# PT08Mpld.net
KiCad netlist of a schematic drawn in EAGLE
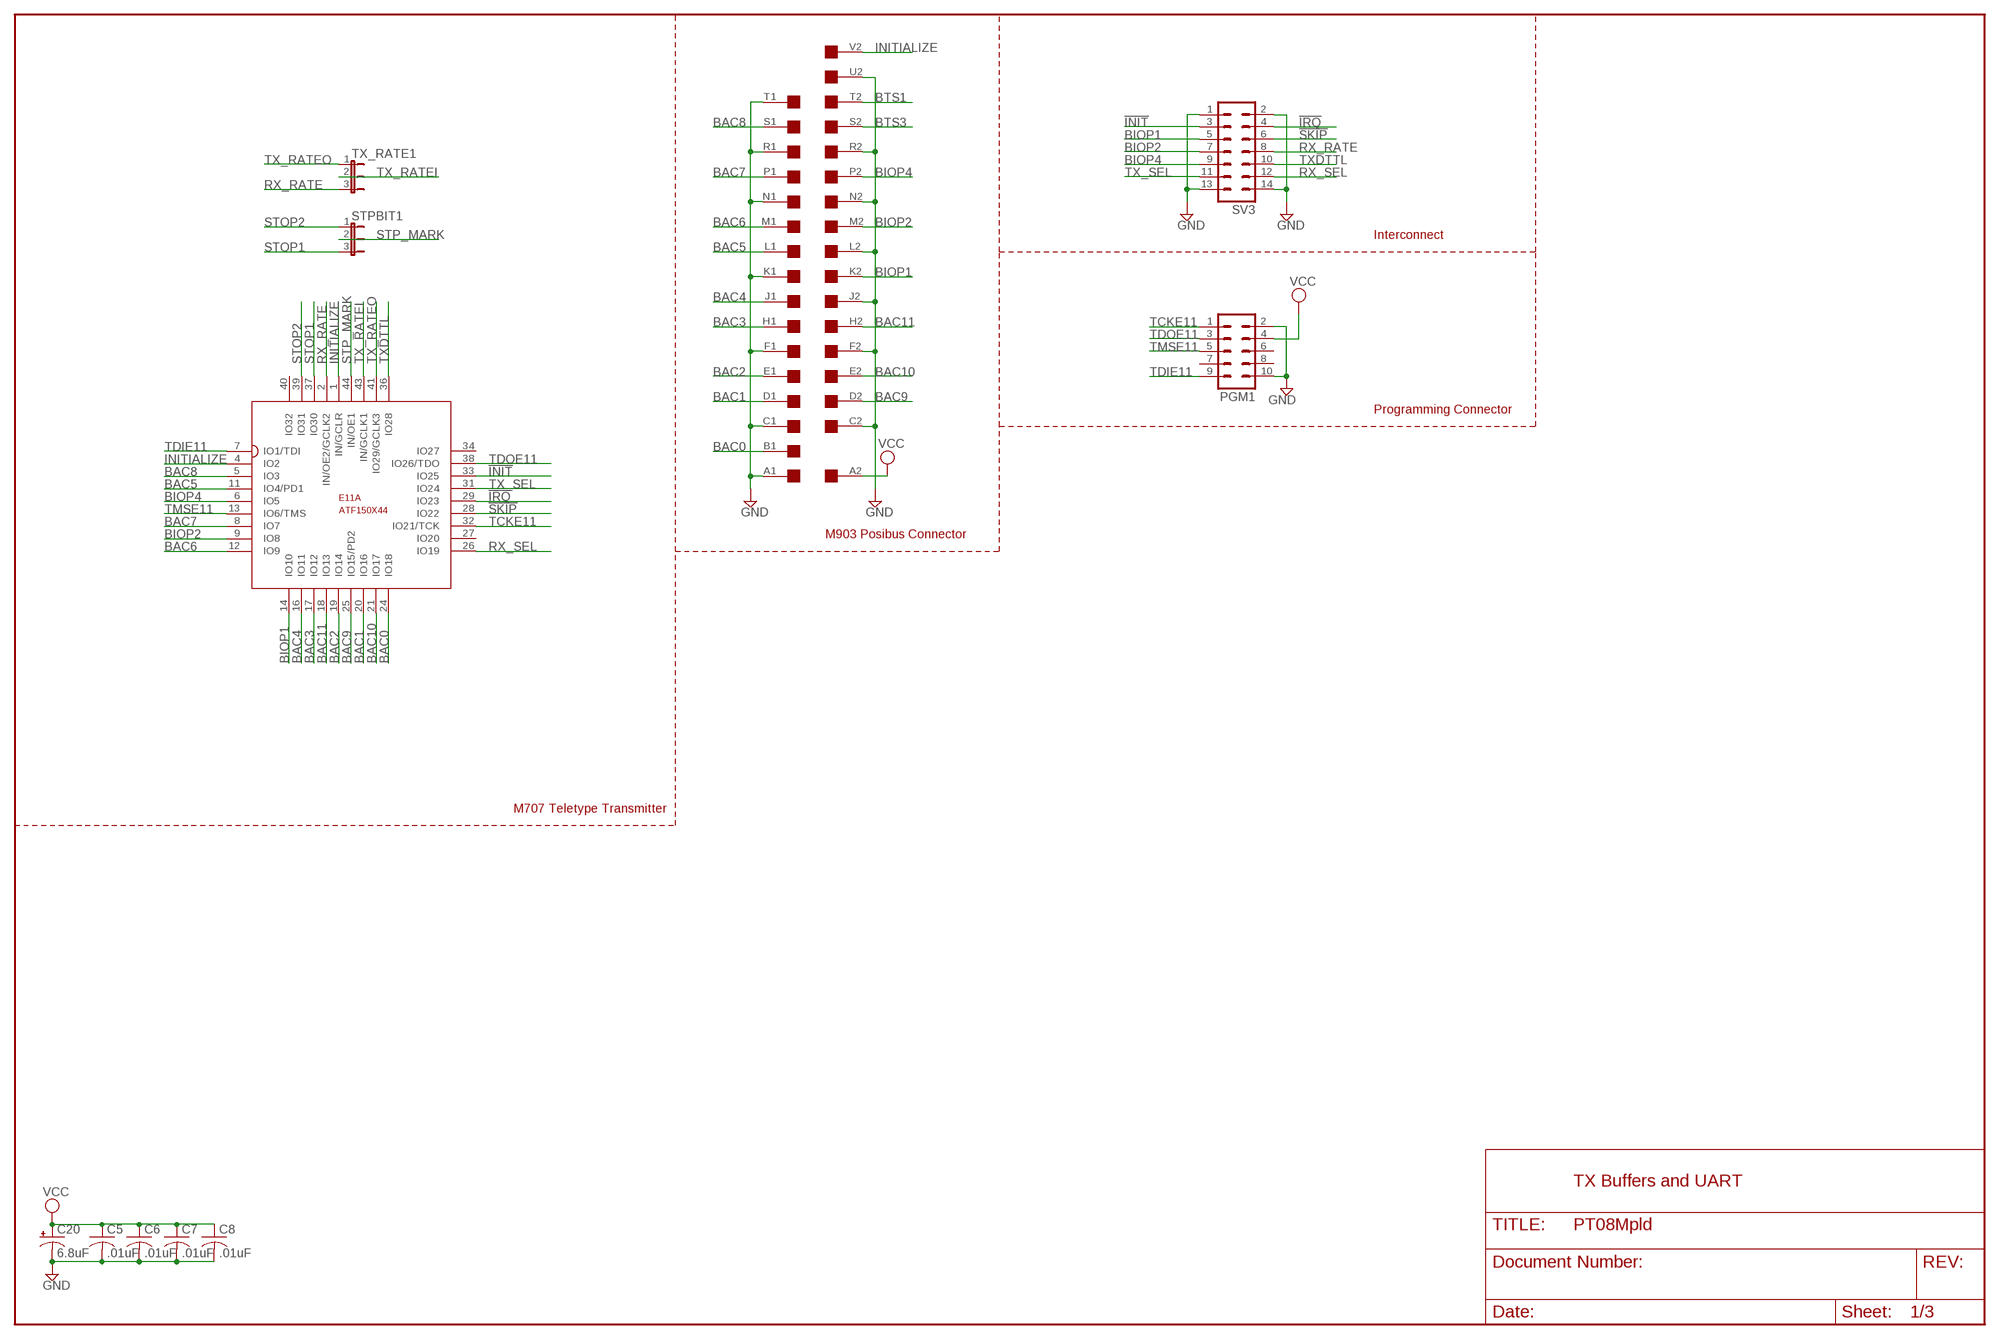
[diagram p0: schematic, sheet 1]
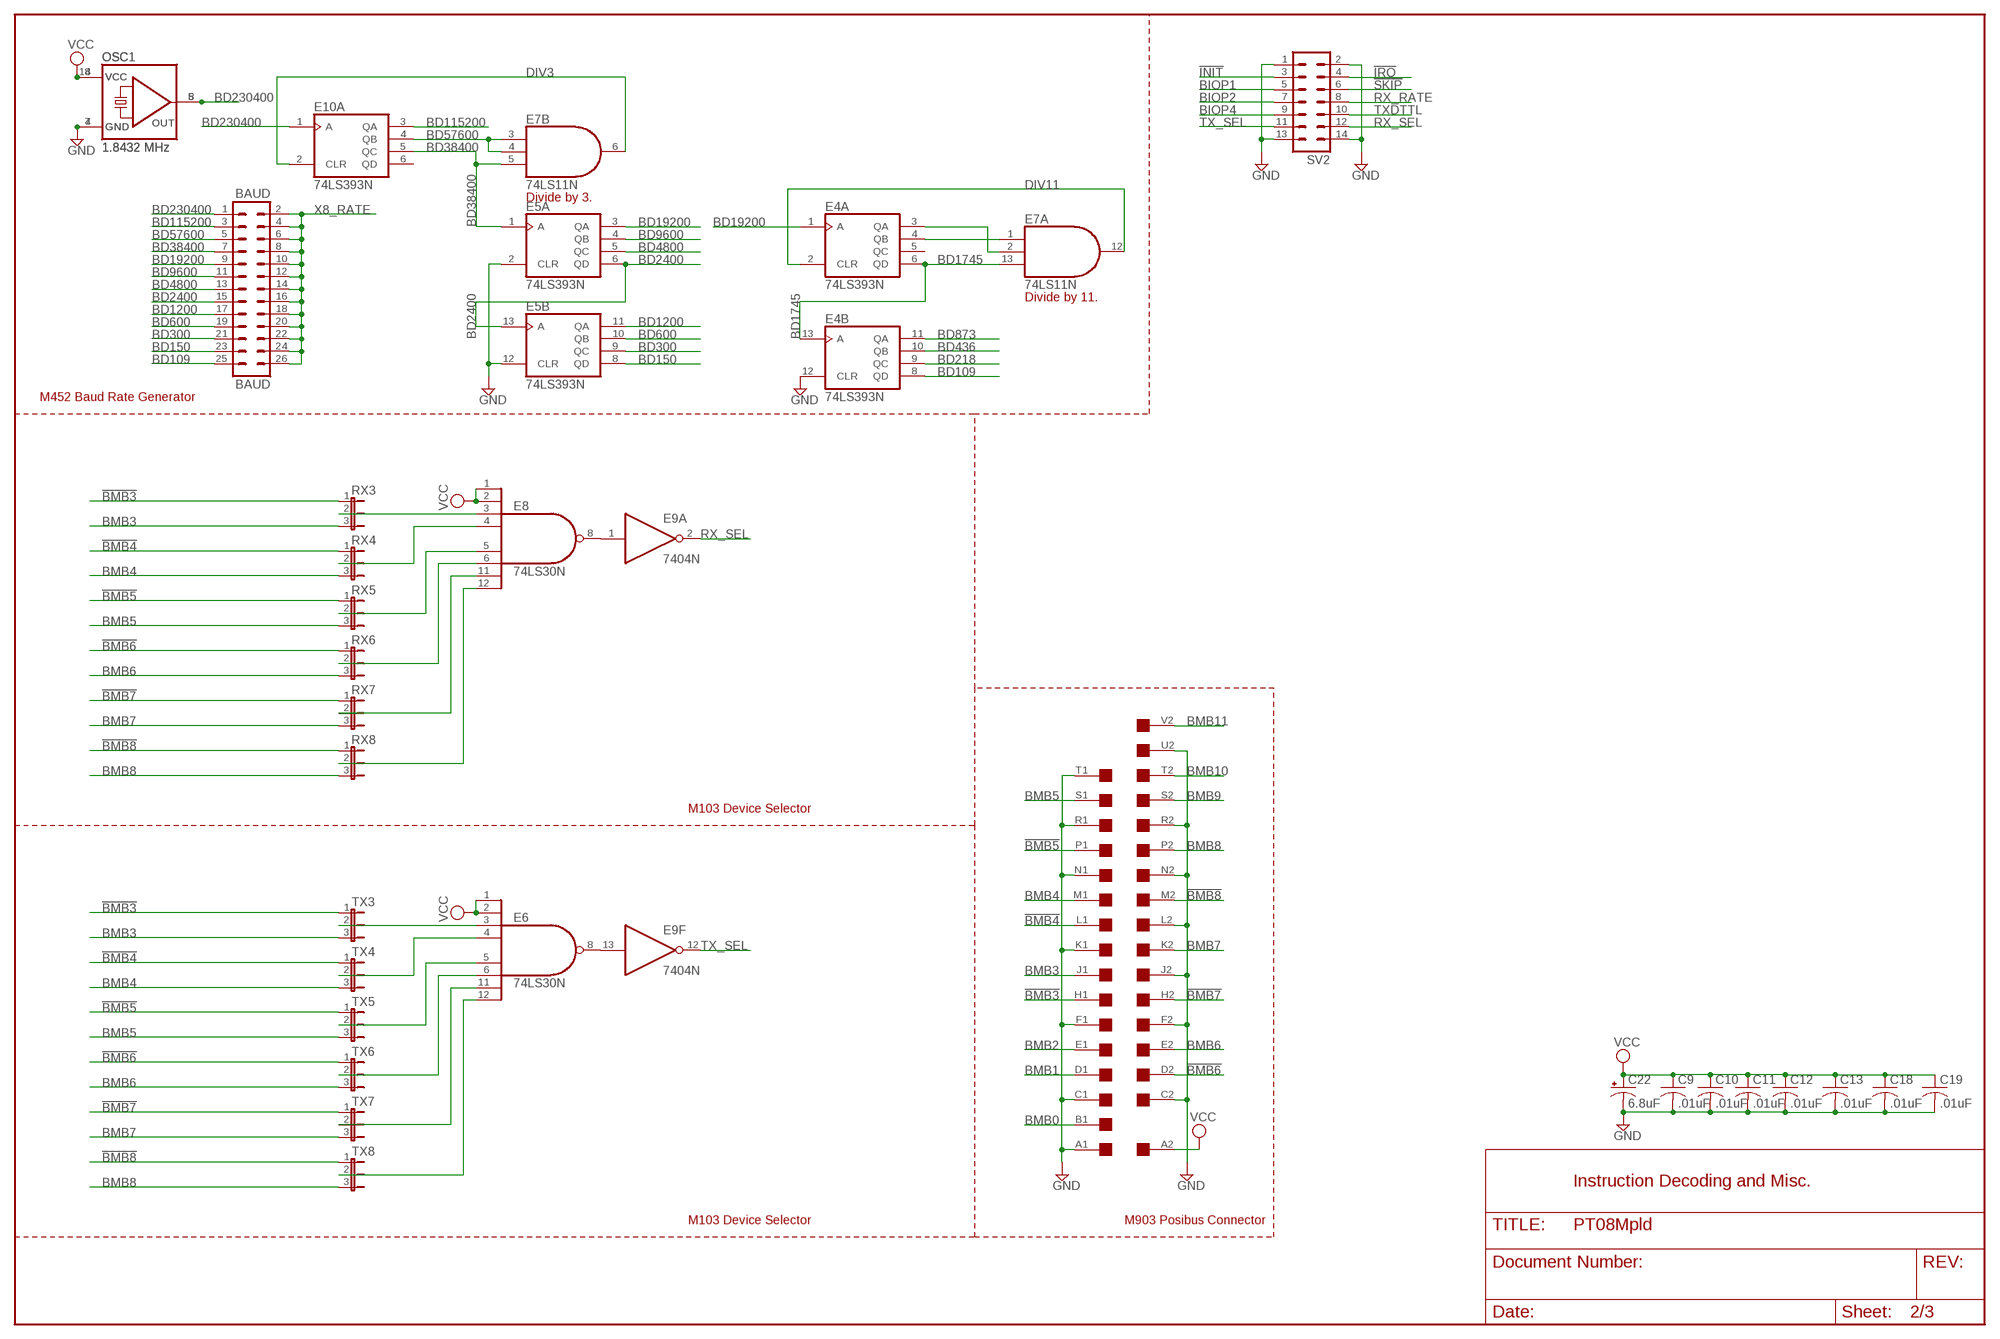
[diagram p1: schematic, sheet 2]
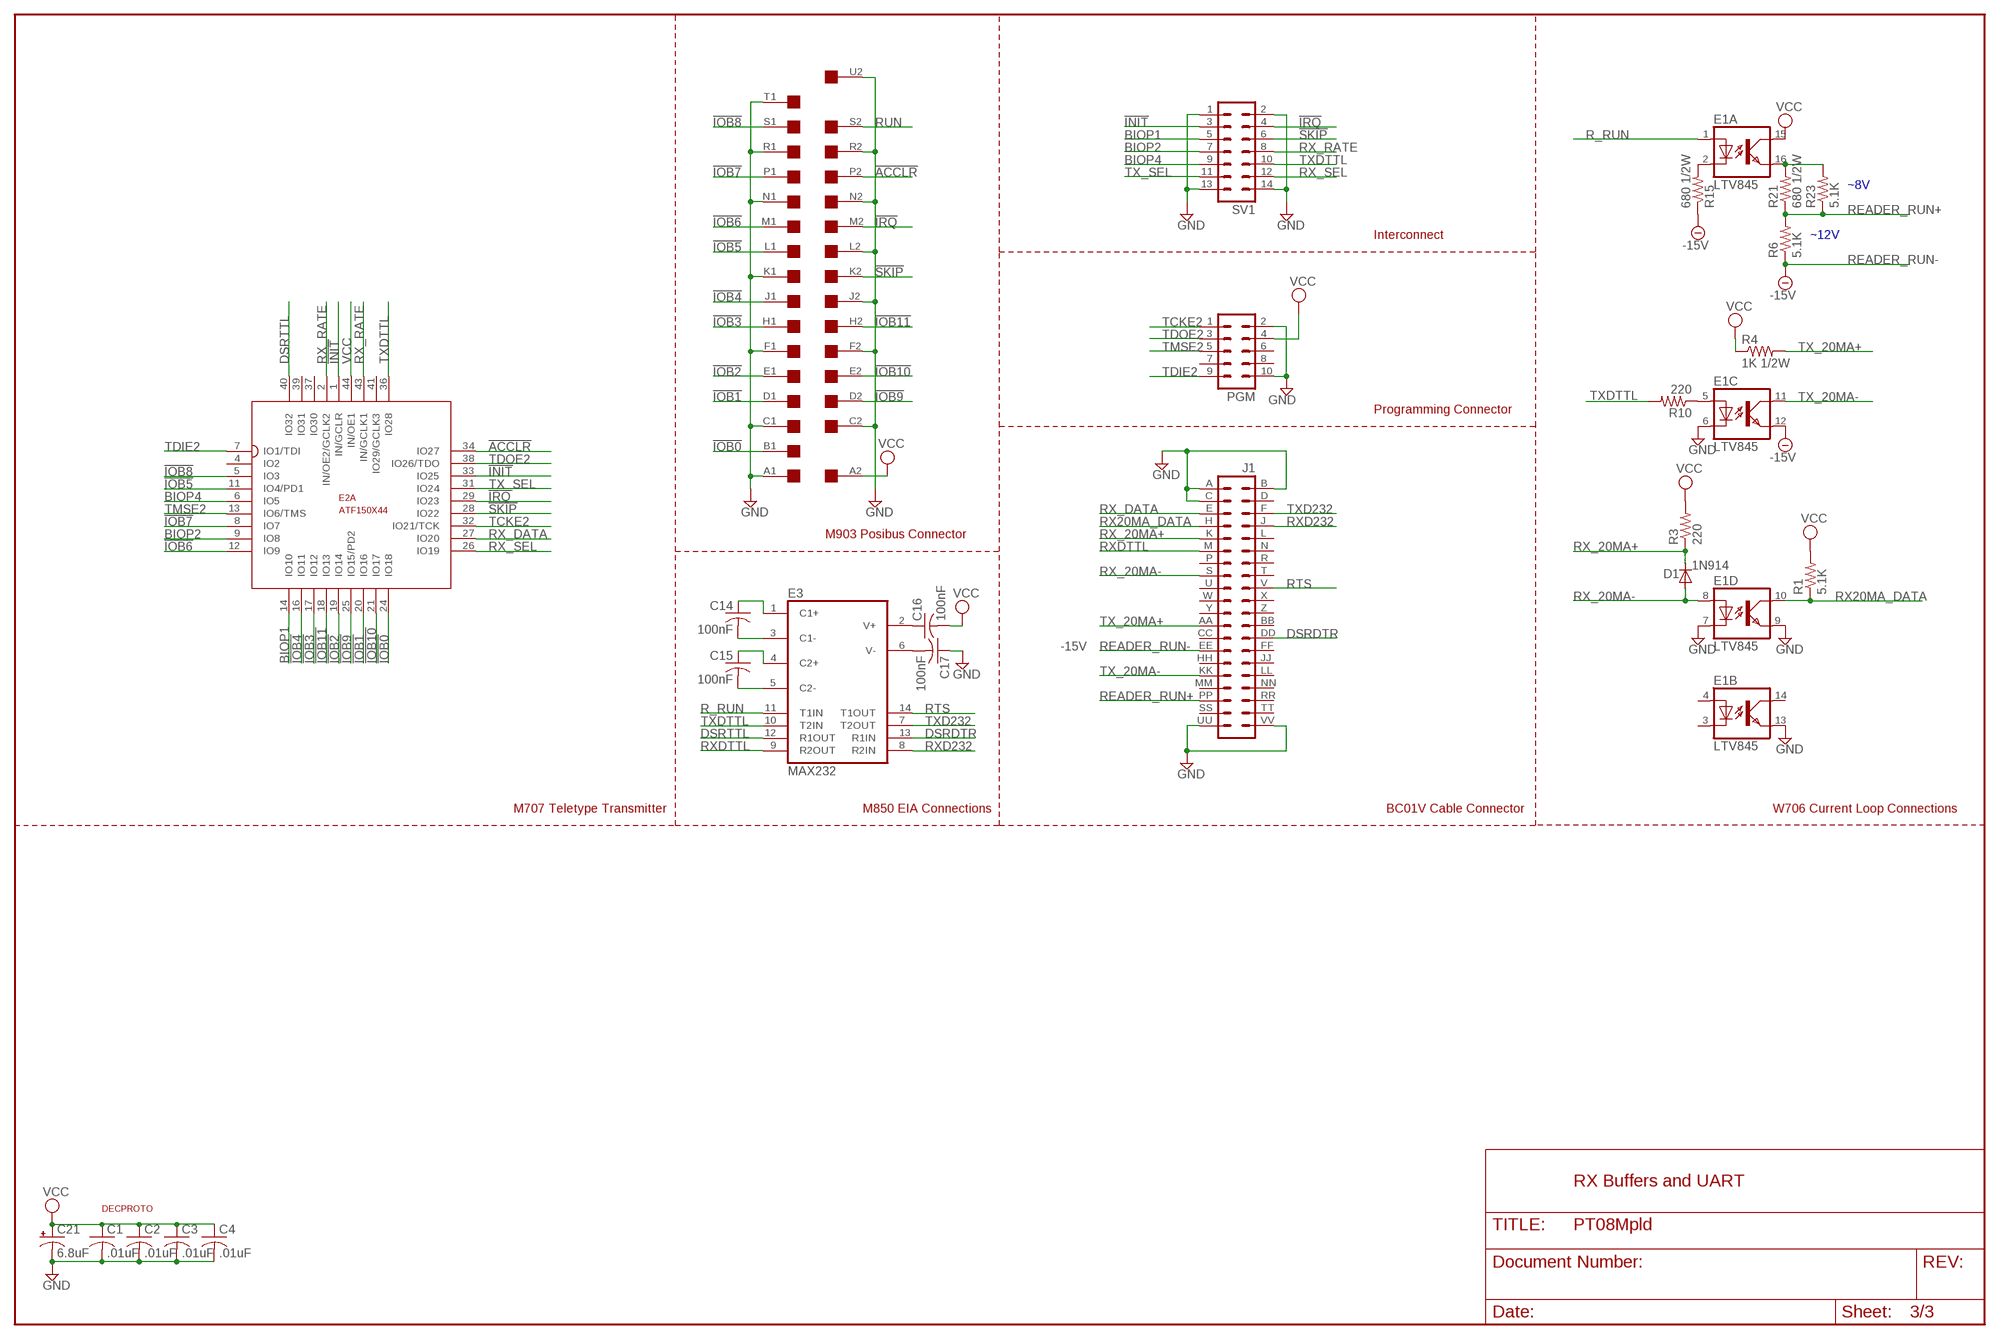
[diagram p2: schematic, sheet 3]

(export (version "E")
  (design (tool "Eeschema 10.0.6"))
  (components
    (comp (ref "C1")
      (value ".01uF")
      (footprint "eagle-import:C050-025X075")
      (libsource (lib "eagle-import") (part "C-US050-025X075"))
    )
    (comp (ref "C2")
      (value ".01uF")
      (footprint "eagle-import:C050-025X075")
      (libsource (lib "eagle-import") (part "C-US050-025X075"))
    )
    (comp (ref "C3")
      (value ".01uF")
      (footprint "eagle-import:C050-025X075")
      (libsource (lib "eagle-import") (part "C-US050-025X075"))
    )
    (comp (ref "C4")
      (value ".01uF")
      (footprint "eagle-import:C050-025X075")
      (libsource (lib "eagle-import") (part "C-US050-025X075"))
    )
    (comp (ref "C14")
      (value "100nF")
      (footprint "eagle-import:C050-025X075")
      (libsource (lib "eagle-import") (part "C-US050-025X075"))
    )
    (comp (ref "C15")
      (value "100nF")
      (footprint "eagle-import:C050-025X075")
      (libsource (lib "eagle-import") (part "C-US050-025X075"))
    )
    (comp (ref "C16")
      (value "100nF")
      (footprint "eagle-import:C050-025X075")
      (libsource (lib "eagle-import") (part "C-US050-025X075"))
    )
    (comp (ref "C17")
      (value "100nF")
      (footprint "eagle-import:C050-025X075")
      (libsource (lib "eagle-import") (part "C-US050-025X075"))
    )
    (comp (ref "C21")
      (value "6.8uF")
      (footprint "eagle-import:E12-8")
      (libsource (lib "eagle-import") (part "CPOL-USE20-8AXIAL"))
    )
    (comp (ref "D1")
      (value "1N914")
      (footprint "eagle-import:DO41-10")
      (libsource (lib "eagle-import") (part "1N4004"))
    )
    (comp (ref "E1")
      (value "LTV845")
      (footprint "eagle-import:DIL16")
      (fields (field (name "MF") "VISHAY/TELEFUNKEN") (field (name "MPN") "ILQ1"))
      (libsource (lib "eagle-import") (part "ILQ1"))
    )
    (comp (ref "E2")
      (value "ATF150X44")
      (footprint "eagle-import:3M44")
      (libsource (lib "eagle-import") (part "ATF150X44"))
    )
    (comp (ref "E3")
      (value "MAX232")
      (footprint "eagle-import:DIL16")
      (fields (field (name "MF") "MAXIM") (field (name "MPN") "MAX232ACPE+"))
      (libsource (lib "eagle-import") (part "MAX232"))
    )
    (comp (ref "IOB")
      (value "EDGE-2CONNECTOR")
      (footprint "eagle-import:EDGE-CON2")
      (libsource (lib "eagle-import") (part "EDGE-2CONNECTOR"))
    )
    (comp (ref "J1")
      (value "DEC40PINH")
      (footprint "eagle-import:DEC40PINH")
      (libsource (lib "eagle-import") (part "DEC40PINH"))
    )
    (comp (ref "PGM")
      (value "ML10")
      (footprint "eagle-import:ML10")
      (libsource (lib "eagle-import") (part "ML10"))
    )
    (comp (ref "R1")
      (value "5.1K")
      (footprint "eagle-import:0207_10")
      (libsource (lib "eagle-import") (part "R-US_0207/10"))
    )
    (comp (ref "R3")
      (value "220")
      (footprint "eagle-import:0207_10")
      (libsource (lib "eagle-import") (part "R-US_0207/10"))
    )
    (comp (ref "R4")
      (value "1K 1/2W")
      (footprint "eagle-import:0207_12")
      (libsource (lib "eagle-import") (part "R-US_0207/12"))
    )
    (comp (ref "R6")
      (value "5.1K")
      (footprint "eagle-import:0207_10")
      (libsource (lib "eagle-import") (part "R-US_0207/10"))
    )
    (comp (ref "R10")
      (value "220")
      (footprint "eagle-import:0207_10")
      (libsource (lib "eagle-import") (part "R-US_0207/10"))
    )
    (comp (ref "R15")
      (value "680 1/2W")
      (footprint "eagle-import:0207_12")
      (libsource (lib "eagle-import") (part "R-US_0207/12"))
    )
    (comp (ref "R21")
      (value "680 1/2W")
      (footprint "eagle-import:0207_12")
      (libsource (lib "eagle-import") (part "R-US_0207/12"))
    )
    (comp (ref "R23")
      (value "5.1K")
      (footprint "eagle-import:0207_10")
      (libsource (lib "eagle-import") (part "R-US_0207/10"))
    )
    (comp (ref "SV1")
      (value "ML14L")
      (footprint "eagle-import:ML14L")
      (libsource (lib "eagle-import") (part "ML14L"))
    )
    (comp (ref "U$2")
      (value "DECPROTO")
      (footprint "eagle-import:DECPROTO111")
      (libsource (lib "eagle-import") (part "DECPROTO"))
    )
    (comp (ref "BAC")
      (value "EDGE-2CONNECTOR")
      (footprint "eagle-import:EDGE-CON2")
      (libsource (lib "eagle-import") (part "EDGE-2CONNECTOR"))
    )
    (comp (ref "C5")
      (value ".01uF")
      (footprint "eagle-import:C050-025X075")
      (libsource (lib "eagle-import") (part "C-US050-025X075"))
    )
    (comp (ref "C6")
      (value ".01uF")
      (footprint "eagle-import:C050-025X075")
      (libsource (lib "eagle-import") (part "C-US050-025X075"))
    )
    (comp (ref "C7")
      (value ".01uF")
      (footprint "eagle-import:C050-025X075")
      (libsource (lib "eagle-import") (part "C-US050-025X075"))
    )
    (comp (ref "C8")
      (value ".01uF")
      (footprint "eagle-import:C050-025X075")
      (libsource (lib "eagle-import") (part "C-US050-025X075"))
    )
    (comp (ref "C20")
      (value "6.8uF")
      (footprint "eagle-import:E12-8")
      (libsource (lib "eagle-import") (part "CPOL-USE20-8AXIAL"))
    )
    (comp (ref "E11")
      (value "ATF150X44")
      (footprint "eagle-import:3M44")
      (libsource (lib "eagle-import") (part "ATF150X44"))
    )
    (comp (ref "PGM1")
      (value "ML10")
      (footprint "eagle-import:ML10")
      (libsource (lib "eagle-import") (part "ML10"))
    )
    (comp (ref "STPBIT1")
      (value "JP2E")
      (footprint "eagle-import:JP2")
      (libsource (lib "eagle-import") (part "JP2E"))
    )
    (comp (ref "SV3")
      (value "ML14L")
      (footprint "eagle-import:ML14L")
      (libsource (lib "eagle-import") (part "ML14L"))
    )
    (comp (ref "TX_RATE1")
      (value "JP2E")
      (footprint "eagle-import:JP2")
      (libsource (lib "eagle-import") (part "JP2E"))
    )
    (comp (ref "BAUD")
      (value "BAUD")
      (footprint "eagle-import:MA13-2")
      (libsource (lib "eagle-import") (part "MA13-2"))
    )
    (comp (ref "BMB")
      (value "EDGE-2CONNECTOR")
      (footprint "eagle-import:EDGE-CON2")
      (libsource (lib "eagle-import") (part "EDGE-2CONNECTOR"))
    )
    (comp (ref "C9")
      (value ".01uF")
      (footprint "eagle-import:C050-025X075")
      (libsource (lib "eagle-import") (part "C-US050-025X075"))
    )
    (comp (ref "C10")
      (value ".01uF")
      (footprint "eagle-import:C050-025X075")
      (libsource (lib "eagle-import") (part "C-US050-025X075"))
    )
    (comp (ref "C11")
      (value ".01uF")
      (footprint "eagle-import:C050-025X075")
      (libsource (lib "eagle-import") (part "C-US050-025X075"))
    )
    (comp (ref "C12")
      (value ".01uF")
      (footprint "eagle-import:C050-025X075")
      (libsource (lib "eagle-import") (part "C-US050-025X075"))
    )
    (comp (ref "C13")
      (value ".01uF")
      (footprint "eagle-import:C050-025X075")
      (libsource (lib "eagle-import") (part "C-US050-025X075"))
    )
    (comp (ref "C18")
      (value ".01uF")
      (footprint "eagle-import:C050-025X075")
      (libsource (lib "eagle-import") (part "C-US050-025X075"))
    )
    (comp (ref "C19")
      (value ".01uF")
      (footprint "eagle-import:C050-025X075")
      (libsource (lib "eagle-import") (part "C-US050-025X075"))
    )
    (comp (ref "C22")
      (value "6.8uF")
      (footprint "eagle-import:E12-8")
      (libsource (lib "eagle-import") (part "CPOL-USE20-8AXIAL"))
    )
    (comp (ref "E4")
      (value "74LS393N")
      (footprint "eagle-import:DIL14")
      (libsource (lib "eagle-import") (part "74393NLS"))
    )
    (comp (ref "E5")
      (value "74LS393N")
      (footprint "eagle-import:DIL14")
      (libsource (lib "eagle-import") (part "74393NLS"))
    )
    (comp (ref "E6")
      (value "74LS30N")
      (footprint "eagle-import:DIL14")
      (libsource (lib "eagle-import") (part "7430NLS"))
    )
    (comp (ref "E7")
      (value "74LS11N")
      (footprint "eagle-import:DIL14")
      (libsource (lib "eagle-import") (part "7411NLS"))
    )
    (comp (ref "E8")
      (value "74LS30N")
      (footprint "eagle-import:DIL14")
      (libsource (lib "eagle-import") (part "7430NLS"))
    )
    (comp (ref "E9")
      (value "7404N")
      (footprint "eagle-import:DIL14")
      (libsource (lib "eagle-import") (part "7404N"))
    )
    (comp (ref "E10")
      (value "74LS393N")
      (footprint "eagle-import:DIL14")
      (libsource (lib "eagle-import") (part "74393NLS"))
    )
    (comp (ref "OSC")
      (value "1.8432 MHz")
      (footprint "eagle-import:DIL08S")
      (libsource (lib "eagle-import") (part "QG5460"))
    )
    (comp (ref "OSC1")
      (value "1.8432 MHz")
      (footprint "eagle-import:DIL14S")
      (libsource (lib "eagle-import") (part "QG5860"))
    )
    (comp (ref "RX3")
      (value "JP2E")
      (footprint "eagle-import:JP2")
      (libsource (lib "eagle-import") (part "JP2E"))
    )
    (comp (ref "RX4")
      (value "JP2E")
      (footprint "eagle-import:JP2")
      (libsource (lib "eagle-import") (part "JP2E"))
    )
    (comp (ref "RX5")
      (value "JP2E")
      (footprint "eagle-import:JP2")
      (libsource (lib "eagle-import") (part "JP2E"))
    )
    (comp (ref "RX6")
      (value "JP2E")
      (footprint "eagle-import:JP2")
      (libsource (lib "eagle-import") (part "JP2E"))
    )
    (comp (ref "RX7")
      (value "JP2E")
      (footprint "eagle-import:JP2")
      (libsource (lib "eagle-import") (part "JP2E"))
    )
    (comp (ref "RX8")
      (value "JP2E")
      (footprint "eagle-import:JP2")
      (libsource (lib "eagle-import") (part "JP2E"))
    )
    (comp (ref "SV2")
      (value "ML14L")
      (footprint "eagle-import:ML14L")
      (libsource (lib "eagle-import") (part "ML14L"))
    )
    (comp (ref "TX3")
      (value "JP2E")
      (footprint "eagle-import:JP2")
      (libsource (lib "eagle-import") (part "JP2E"))
    )
    (comp (ref "TX4")
      (value "JP2E")
      (footprint "eagle-import:JP2")
      (libsource (lib "eagle-import") (part "JP2E"))
    )
    (comp (ref "TX5")
      (value "JP2E")
      (footprint "eagle-import:JP2")
      (libsource (lib "eagle-import") (part "JP2E"))
    )
    (comp (ref "TX6")
      (value "JP2E")
      (footprint "eagle-import:JP2")
      (libsource (lib "eagle-import") (part "JP2E"))
    )
    (comp (ref "TX7")
      (value "JP2E")
      (footprint "eagle-import:JP2")
      (libsource (lib "eagle-import") (part "JP2E"))
    )
    (comp (ref "TX8")
      (value "JP2E")
      (footprint "eagle-import:JP2")
      (libsource (lib "eagle-import") (part "JP2E"))
    )
  )
  (nets
    (net (code "1") (name "-15V") (class "Default")
      (node (ref "E1") (pin "12") (pinfunction "EMIT_12") (pintype "passive"))
      (node (ref "J1") (pin "EE") (pinfunction "27_EE") (pintype "bidirectional"))
      (node (ref "R15") (pin "1") (pinfunction "1_1") (pintype "passive"))
      (node (ref "R6") (pin "1") (pinfunction "1_1") (pintype "passive"))
    )
    (net (code "2") (name "BAC0") (class "Default")
      (node (ref "BAC") (pin "B1") (pinfunction "1_B1") (pintype "bidirectional"))
      (node (ref "E11") (pin "24") (pinfunction "IO18_24") (pintype "bidirectional"))
    )
    (net (code "3") (name "BAC1") (class "Default")
      (node (ref "BAC") (pin "D1") (pinfunction "1_D1") (pintype "bidirectional"))
      (node (ref "E11") (pin "20") (pinfunction "IO16_20") (pintype "bidirectional"))
    )
    (net (code "4") (name "BAC2") (class "Default")
      (node (ref "BAC") (pin "E1") (pinfunction "1_E1") (pintype "bidirectional"))
      (node (ref "E11") (pin "19") (pinfunction "IO14_19") (pintype "bidirectional"))
    )
    (net (code "5") (name "BAC3") (class "Default")
      (node (ref "BAC") (pin "H1") (pinfunction "1_H1") (pintype "bidirectional"))
      (node (ref "E11") (pin "17") (pinfunction "IO12_17") (pintype "bidirectional"))
    )
    (net (code "6") (name "BAC4") (class "Default")
      (node (ref "BAC") (pin "J1") (pinfunction "1_J1") (pintype "bidirectional"))
      (node (ref "E11") (pin "16") (pinfunction "IO11_16") (pintype "bidirectional"))
    )
    (net (code "7") (name "BAC5") (class "Default")
      (node (ref "BAC") (pin "L1") (pinfunction "1_L1") (pintype "bidirectional"))
      (node (ref "E11") (pin "11") (pinfunction "IO4/PD1_11") (pintype "bidirectional"))
    )
    (net (code "8") (name "BAC6") (class "Default")
      (node (ref "BAC") (pin "M1") (pinfunction "1_M1") (pintype "bidirectional"))
      (node (ref "E11") (pin "12") (pinfunction "IO9_12") (pintype "bidirectional"))
    )
    (net (code "9") (name "BAC7") (class "Default")
      (node (ref "BAC") (pin "P1") (pinfunction "1_P1") (pintype "bidirectional"))
      (node (ref "E11") (pin "8") (pinfunction "IO7_8") (pintype "bidirectional"))
    )
    (net (code "10") (name "BAC8") (class "Default")
      (node (ref "BAC") (pin "S1") (pinfunction "1_S1") (pintype "bidirectional"))
      (node (ref "E11") (pin "5") (pinfunction "IO3_5") (pintype "bidirectional"))
    )
    (net (code "11") (name "BAC9") (class "Default")
      (node (ref "BAC") (pin "D2") (pinfunction "1_D2") (pintype "bidirectional"))
      (node (ref "E11") (pin "25") (pinfunction "IO15/PD2_25") (pintype "bidirectional"))
    )
    (net (code "12") (name "BAC10") (class "Default")
      (node (ref "BAC") (pin "E2") (pinfunction "1_E2") (pintype "bidirectional"))
      (node (ref "E11") (pin "21") (pinfunction "IO17_21") (pintype "bidirectional"))
    )
    (net (code "13") (name "BAC11") (class "Default")
      (node (ref "BAC") (pin "H2") (pinfunction "1_H2") (pintype "bidirectional"))
      (node (ref "E11") (pin "18") (pinfunction "IO13_18") (pintype "bidirectional"))
    )
    (net (code "14") (name "BD109") (class "Default")
      (node (ref "BAUD") (pin "25") (pinfunction "25_25") (pintype "passive"))
      (node (ref "E4") (pin "8") (pinfunction "QD_8") (pintype "output"))
    )
    (net (code "15") (name "BD150") (class "Default")
      (node (ref "BAUD") (pin "23") (pinfunction "23_23") (pintype "passive"))
      (node (ref "E5") (pin "8") (pinfunction "QD_8") (pintype "output"))
    )
    (net (code "16") (name "BD218") (class "Default")
      (node (ref "E4") (pin "9") (pinfunction "QC_9") (pintype "output"))
    )
    (net (code "17") (name "BD300") (class "Default")
      (node (ref "BAUD") (pin "21") (pinfunction "21_21") (pintype "passive"))
      (node (ref "E5") (pin "9") (pinfunction "QC_9") (pintype "output"))
    )
    (net (code "18") (name "BD436") (class "Default")
      (node (ref "E4") (pin "10") (pinfunction "QB_10") (pintype "output"))
    )
    (net (code "19") (name "BD600") (class "Default")
      (node (ref "BAUD") (pin "19") (pinfunction "19_19") (pintype "passive"))
      (node (ref "E5") (pin "10") (pinfunction "QB_10") (pintype "output"))
    )
    (net (code "20") (name "BD873") (class "Default")
      (node (ref "E4") (pin "11") (pinfunction "QA_11") (pintype "output"))
    )
    (net (code "21") (name "BD1200") (class "Default")
      (node (ref "BAUD") (pin "17") (pinfunction "17_17") (pintype "passive"))
      (node (ref "E5") (pin "11") (pinfunction "QA_11") (pintype "output"))
    )
    (net (code "22") (name "BD1745") (class "Default")
      (node (ref "E4") (pin "13") (pinfunction "A_13") (pintype "input"))
      (node (ref "E4") (pin "6") (pinfunction "QD_6") (pintype "output"))
      (node (ref "E7") (pin "13") (pinfunction "I2_13") (pintype "input"))
    )
    (net (code "23") (name "BD2400") (class "Default")
      (node (ref "BAUD") (pin "15") (pinfunction "15_15") (pintype "passive"))
      (node (ref "E5") (pin "13") (pinfunction "A_13") (pintype "input"))
      (node (ref "E5") (pin "6") (pinfunction "QD_6") (pintype "output"))
    )
    (net (code "24") (name "BD4800") (class "Default")
      (node (ref "BAUD") (pin "13") (pinfunction "13_13") (pintype "passive"))
      (node (ref "E5") (pin "5") (pinfunction "QC_5") (pintype "output"))
    )
    (net (code "25") (name "BD9600") (class "Default")
      (node (ref "BAUD") (pin "11") (pinfunction "11_11") (pintype "passive"))
      (node (ref "E5") (pin "4") (pinfunction "QB_4") (pintype "output"))
    )
    (net (code "26") (name "BD19200") (class "Default")
      (node (ref "BAUD") (pin "9") (pinfunction "9_9") (pintype "passive"))
      (node (ref "E4") (pin "1") (pinfunction "A_1") (pintype "input"))
      (node (ref "E5") (pin "3") (pinfunction "QA_3") (pintype "output"))
    )
    (net (code "27") (name "BD38400") (class "Default")
      (node (ref "BAUD") (pin "7") (pinfunction "7_7") (pintype "passive"))
      (node (ref "E10") (pin "5") (pinfunction "QC_5") (pintype "output"))
      (node (ref "E5") (pin "1") (pinfunction "A_1") (pintype "input"))
      (node (ref "E7") (pin "5") (pinfunction "I2_5") (pintype "input"))
    )
    (net (code "28") (name "BD57600") (class "Default")
      (node (ref "BAUD") (pin "5") (pinfunction "5_5") (pintype "passive"))
      (node (ref "E10") (pin "4") (pinfunction "QB_4") (pintype "output"))
      (node (ref "E7") (pin "3") (pinfunction "I0_3") (pintype "input"))
      (node (ref "E7") (pin "4") (pinfunction "I1_4") (pintype "input"))
    )
    (net (code "29") (name "BD115200") (class "Default")
      (node (ref "BAUD") (pin "3") (pinfunction "3_3") (pintype "passive"))
      (node (ref "E10") (pin "3") (pinfunction "QA_3") (pintype "output"))
    )
    (net (code "30") (name "BD230400") (class "Default")
      (node (ref "BAUD") (pin "1") (pinfunction "1_1") (pintype "passive"))
      (node (ref "E10") (pin "1") (pinfunction "A_1") (pintype "input"))
      (node (ref "OSC") (pin "5") (pinfunction "OUT_5") (pintype "output"))
      (node (ref "OSC1") (pin "8") (pinfunction "OUT_8") (pintype "output"))
    )
    (net (code "31") (name "BIOP1") (class "Default")
      (node (ref "BAC") (pin "K2") (pinfunction "1_K2") (pintype "bidirectional"))
      (node (ref "E11") (pin "14") (pinfunction "IO10_14") (pintype "bidirectional"))
      (node (ref "E2") (pin "14") (pinfunction "IO10_14") (pintype "bidirectional"))
      (node (ref "SV1") (pin "5") (pinfunction "5_5") (pintype "passive"))
      (node (ref "SV2") (pin "5") (pinfunction "5_5") (pintype "passive"))
      (node (ref "SV3") (pin "5") (pinfunction "5_5") (pintype "passive"))
    )
    (net (code "32") (name "BIOP2") (class "Default")
      (node (ref "BAC") (pin "M2") (pinfunction "1_M2") (pintype "bidirectional"))
      (node (ref "E11") (pin "9") (pinfunction "IO8_9") (pintype "bidirectional"))
      (node (ref "E2") (pin "9") (pinfunction "IO8_9") (pintype "bidirectional"))
      (node (ref "SV1") (pin "7") (pinfunction "7_7") (pintype "passive"))
      (node (ref "SV2") (pin "7") (pinfunction "7_7") (pintype "passive"))
      (node (ref "SV3") (pin "7") (pinfunction "7_7") (pintype "passive"))
    )
    (net (code "33") (name "BIOP4") (class "Default")
      (node (ref "BAC") (pin "P2") (pinfunction "1_P2") (pintype "bidirectional"))
      (node (ref "E11") (pin "6") (pinfunction "IO5_6") (pintype "bidirectional"))
      (node (ref "E2") (pin "6") (pinfunction "IO5_6") (pintype "bidirectional"))
      (node (ref "SV1") (pin "9") (pinfunction "9_9") (pintype "passive"))
      (node (ref "SV2") (pin "9") (pinfunction "9_9") (pintype "passive"))
      (node (ref "SV3") (pin "9") (pinfunction "9_9") (pintype "passive"))
    )
    (net (code "34") (name "BMB0") (class "Default")
      (node (ref "BMB") (pin "B1") (pinfunction "1_B1") (pintype "bidirectional"))
    )
    (net (code "35") (name "BMB1") (class "Default")
      (node (ref "BMB") (pin "D1") (pinfunction "1_D1") (pintype "bidirectional"))
    )
    (net (code "36") (name "BMB2") (class "Default")
      (node (ref "BMB") (pin "E1") (pinfunction "1_E1") (pintype "bidirectional"))
    )
    (net (code "37") (name "BMB3") (class "Default")
      (node (ref "BMB") (pin "J1") (pinfunction "1_J1") (pintype "bidirectional"))
      (node (ref "RX3") (pin "3") (pinfunction "3_3") (pintype "passive"))
      (node (ref "TX3") (pin "3") (pinfunction "3_3") (pintype "passive"))
    )
    (net (code "38") (name "BMB4") (class "Default")
      (node (ref "BMB") (pin "M1") (pinfunction "1_M1") (pintype "bidirectional"))
      (node (ref "RX4") (pin "3") (pinfunction "3_3") (pintype "passive"))
      (node (ref "TX4") (pin "3") (pinfunction "3_3") (pintype "passive"))
    )
    (net (code "39") (name "BMB5") (class "Default")
      (node (ref "BMB") (pin "S1") (pinfunction "1_S1") (pintype "bidirectional"))
      (node (ref "RX5") (pin "3") (pinfunction "3_3") (pintype "passive"))
      (node (ref "TX5") (pin "3") (pinfunction "3_3") (pintype "passive"))
    )
    (net (code "40") (name "BMB6") (class "Default")
      (node (ref "BMB") (pin "E2") (pinfunction "1_E2") (pintype "bidirectional"))
      (node (ref "RX6") (pin "3") (pinfunction "3_3") (pintype "passive"))
      (node (ref "TX6") (pin "3") (pinfunction "3_3") (pintype "passive"))
    )
    (net (code "41") (name "BMB7") (class "Default")
      (node (ref "BMB") (pin "K2") (pinfunction "1_K2") (pintype "bidirectional"))
      (node (ref "RX7") (pin "3") (pinfunction "3_3") (pintype "passive"))
      (node (ref "TX7") (pin "3") (pinfunction "3_3") (pintype "passive"))
    )
    (net (code "42") (name "BMB8") (class "Default")
      (node (ref "BMB") (pin "P2") (pinfunction "1_P2") (pintype "bidirectional"))
      (node (ref "RX8") (pin "3") (pinfunction "3_3") (pintype "passive"))
      (node (ref "TX8") (pin "3") (pinfunction "3_3") (pintype "passive"))
    )
    (net (code "43") (name "BMB9") (class "Default")
      (node (ref "BMB") (pin "S2") (pinfunction "1_S2") (pintype "bidirectional"))
    )
    (net (code "44") (name "BMB10") (class "Default")
      (node (ref "BMB") (pin "T2") (pinfunction "1_T2") (pintype "bidirectional"))
    )
    (net (code "45") (name "BMB11") (class "Default")
      (node (ref "BMB") (pin "V2") (pinfunction "1_V2") (pintype "bidirectional"))
    )
    (net (code "46") (name "BTS1") (class "Default")
      (node (ref "BAC") (pin "T2") (pinfunction "1_T2") (pintype "bidirectional"))
    )
    (net (code "47") (name "BTS3") (class "Default")
      (node (ref "BAC") (pin "S2") (pinfunction "1_S2") (pintype "bidirectional"))
    )
    (net (code "48") (name "DIV3") (class "Default")
      (node (ref "E10") (pin "2") (pinfunction "CLR_2") (pintype "input"))
      (node (ref "E7") (pin "6") (pinfunction "O_6") (pintype "output"))
    )
    (net (code "49") (name "DIV11") (class "Default")
      (node (ref "E4") (pin "2") (pinfunction "CLR_2") (pintype "input"))
      (node (ref "E7") (pin "12") (pinfunction "O_12") (pintype "output"))
    )
    (net (code "50") (name "DSRDTR") (class "Default")
      (node (ref "E3") (pin "13") (pinfunction "R1IN_13") (pintype "input"))
      (node (ref "J1") (pin "DD") (pinfunction "26_DD") (pintype "bidirectional"))
    )
    (net (code "51") (name "DSRTTL") (class "Default")
      (node (ref "E2") (pin "40") (pinfunction "IO32_40") (pintype "bidirectional"))
      (node (ref "E3") (pin "12") (pinfunction "R1OUT_12") (pintype "output"))
    )
    (net (code "52") (name "GND") (class "Default")
      (node (ref "BAC") (pin "A1") (pinfunction "1_A1") (pintype "bidirectional"))
      (node (ref "BAC") (pin "C1") (pinfunction "1_C1") (pintype "bidirectional"))
      (node (ref "BAC") (pin "C2") (pinfunction "1_C2") (pintype "bidirectional"))
      (node (ref "BAC") (pin "F1") (pinfunction "1_F1") (pintype "bidirectional"))
      (node (ref "BAC") (pin "F2") (pinfunction "1_F2") (pintype "bidirectional"))
      (node (ref "BAC") (pin "J2") (pinfunction "1_J2") (pintype "bidirectional"))
      (node (ref "BAC") (pin "K1") (pinfunction "1_K1") (pintype "bidirectional"))
      (node (ref "BAC") (pin "L2") (pinfunction "1_L2") (pintype "bidirectional"))
      (node (ref "BAC") (pin "N1") (pinfunction "1_N1") (pintype "bidirectional"))
      (node (ref "BAC") (pin "N2") (pinfunction "1_N2") (pintype "bidirectional"))
      (node (ref "BAC") (pin "R1") (pinfunction "1_R1") (pintype "bidirectional"))
      (node (ref "BAC") (pin "R2") (pinfunction "1_R2") (pintype "bidirectional"))
      (node (ref "BAC") (pin "T1") (pinfunction "1_T1") (pintype "bidirectional"))
      (node (ref "BAC") (pin "U2") (pinfunction "1_U2") (pintype "bidirectional"))
      (node (ref "BMB") (pin "A1") (pinfunction "1_A1") (pintype "bidirectional"))
      (node (ref "BMB") (pin "C1") (pinfunction "1_C1") (pintype "bidirectional"))
      (node (ref "BMB") (pin "C2") (pinfunction "1_C2") (pintype "bidirectional"))
      (node (ref "BMB") (pin "F1") (pinfunction "1_F1") (pintype "bidirectional"))
      (node (ref "BMB") (pin "F2") (pinfunction "1_F2") (pintype "bidirectional"))
      (node (ref "BMB") (pin "J2") (pinfunction "1_J2") (pintype "bidirectional"))
      (node (ref "BMB") (pin "K1") (pinfunction "1_K1") (pintype "bidirectional"))
      (node (ref "BMB") (pin "L2") (pinfunction "1_L2") (pintype "bidirectional"))
      (node (ref "BMB") (pin "N1") (pinfunction "1_N1") (pintype "bidirectional"))
      (node (ref "BMB") (pin "N2") (pinfunction "1_N2") (pintype "bidirectional"))
      (node (ref "BMB") (pin "R1") (pinfunction "1_R1") (pintype "bidirectional"))
      (node (ref "BMB") (pin "R2") (pinfunction "1_R2") (pintype "bidirectional"))
      (node (ref "BMB") (pin "T1") (pinfunction "1_T1") (pintype "bidirectional"))
      (node (ref "BMB") (pin "U2") (pinfunction "1_U2") (pintype "bidirectional"))
      (node (ref "C1") (pin "2") (pinfunction "2_2") (pintype "passive"))
      (node (ref "C10") (pin "2") (pinfunction "2_2") (pintype "passive"))
      (node (ref "C11") (pin "2") (pinfunction "2_2") (pintype "passive"))
      (node (ref "C12") (pin "2") (pinfunction "2_2") (pintype "passive"))
      (node (ref "C13") (pin "2") (pinfunction "2_2") (pintype "passive"))
      (node (ref "C17") (pin "1") (pinfunction "1_1") (pintype "passive"))
      (node (ref "C18") (pin "2") (pinfunction "2_2") (pintype "passive"))
      (node (ref "C19") (pin "2") (pinfunction "2_2") (pintype "passive"))
      (node (ref "C2") (pin "2") (pinfunction "2_2") (pintype "passive"))
      (node (ref "C20") (pin "-") (pinfunction "-_-") (pintype "passive"))
      (node (ref "C21") (pin "-") (pinfunction "-_-") (pintype "passive"))
      (node (ref "C22") (pin "-") (pinfunction "-_-") (pintype "passive"))
      (node (ref "C3") (pin "2") (pinfunction "2_2") (pintype "passive"))
      (node (ref "C4") (pin "2") (pinfunction "2_2") (pintype "passive"))
      (node (ref "C5") (pin "2") (pinfunction "2_2") (pintype "passive"))
      (node (ref "C6") (pin "2") (pinfunction "2_2") (pintype "passive"))
      (node (ref "C7") (pin "2") (pinfunction "2_2") (pintype "passive"))
      (node (ref "C8") (pin "2") (pinfunction "2_2") (pintype "passive"))
      (node (ref "C9") (pin "2") (pinfunction "2_2") (pintype "passive"))
      (node (ref "E1") (pin "13") (pinfunction "EMIT_13") (pintype "passive"))
      (node (ref "E1") (pin "6") (pinfunction "C_6") (pintype "passive"))
      (node (ref "E1") (pin "7") (pinfunction "C_7") (pintype "passive"))
      (node (ref "E1") (pin "9") (pinfunction "EMIT_9") (pintype "passive"))
      (node (ref "E4") (pin "12") (pinfunction "CLR_12") (pintype "input"))
      (node (ref "E5") (pin "12") (pinfunction "CLR_12") (pintype "input"))
      (node (ref "E5") (pin "2") (pinfunction "CLR_2") (pintype "input"))
      (node (ref "IOB") (pin "A1") (pinfunction "1_A1") (pintype "bidirectional"))
      (node (ref "IOB") (pin "C1") (pinfunction "1_C1") (pintype "bidirectional"))
      (node (ref "IOB") (pin "C2") (pinfunction "1_C2") (pintype "bidirectional"))
      (node (ref "IOB") (pin "F1") (pinfunction "1_F1") (pintype "bidirectional"))
      (node (ref "IOB") (pin "F2") (pinfunction "1_F2") (pintype "bidirectional"))
      (node (ref "IOB") (pin "J2") (pinfunction "1_J2") (pintype "bidirectional"))
      (node (ref "IOB") (pin "K1") (pinfunction "1_K1") (pintype "bidirectional"))
      (node (ref "IOB") (pin "L2") (pinfunction "1_L2") (pintype "bidirectional"))
      (node (ref "IOB") (pin "N1") (pinfunction "1_N1") (pintype "bidirectional"))
      (node (ref "IOB") (pin "N2") (pinfunction "1_N2") (pintype "bidirectional"))
      (node (ref "IOB") (pin "R1") (pinfunction "1_R1") (pintype "bidirectional"))
      (node (ref "IOB") (pin "R2") (pinfunction "1_R2") (pintype "bidirectional"))
      (node (ref "IOB") (pin "T1") (pinfunction "1_T1") (pintype "bidirectional"))
      (node (ref "IOB") (pin "U2") (pinfunction "1_U2") (pintype "bidirectional"))
      (node (ref "J1") (pin "A") (pinfunction "1_A") (pintype "bidirectional"))
      (node (ref "J1") (pin "B") (pinfunction "2_B") (pintype "bidirectional"))
      (node (ref "J1") (pin "C") (pinfunction "3_C") (pintype "bidirectional"))
      (node (ref "J1") (pin "UU") (pinfunction "39_UU") (pintype "bidirectional"))
      (node (ref "J1") (pin "VV") (pinfunction "40_VV") (pintype "bidirectional"))
      (node (ref "OSC") (pin "4") (pinfunction "GND_4") (pintype "power_in"))
      (node (ref "OSC1") (pin "7") (pinfunction "GND_7") (pintype "power_in"))
      (node (ref "PGM") (pin "10") (pinfunction "10_10") (pintype "passive"))
      (node (ref "PGM") (pin "2") (pinfunction "2_2") (pintype "passive"))
      (node (ref "PGM1") (pin "10") (pinfunction "10_10") (pintype "passive"))
      (node (ref "PGM1") (pin "2") (pinfunction "2_2") (pintype "passive"))
      (node (ref "SV1") (pin "1") (pinfunction "1_1") (pintype "passive"))
      (node (ref "SV1") (pin "13") (pinfunction "13_13") (pintype "passive"))
      (node (ref "SV1") (pin "14") (pinfunction "14_14") (pintype "passive"))
      (node (ref "SV1") (pin "2") (pinfunction "2_2") (pintype "passive"))
      (node (ref "SV2") (pin "1") (pinfunction "1_1") (pintype "passive"))
      (node (ref "SV2") (pin "13") (pinfunction "13_13") (pintype "passive"))
      (node (ref "SV2") (pin "14") (pinfunction "14_14") (pintype "passive"))
      (node (ref "SV2") (pin "2") (pinfunction "2_2") (pintype "passive"))
      (node (ref "SV3") (pin "1") (pinfunction "1_1") (pintype "passive"))
      (node (ref "SV3") (pin "13") (pinfunction "13_13") (pintype "passive"))
      (node (ref "SV3") (pin "14") (pinfunction "14_14") (pintype "passive"))
      (node (ref "SV3") (pin "2") (pinfunction "2_2") (pintype "passive"))
    )
    (net (code "53") (name "INITIALIZE") (class "Default")
      (node (ref "BAC") (pin "V2") (pinfunction "1_V2") (pintype "bidirectional"))
      (node (ref "E11") (pin "1") (pinfunction "IN/GCLR_1") (pintype "input"))
      (node (ref "E11") (pin "4") (pinfunction "IO2_4") (pintype "bidirectional"))
    )
    (net (code "54") (name "Net-(E1A-C)") (class "Default")
      (node (ref "E1") (pin "2") (pinfunction "C_2") (pintype "passive"))
      (node (ref "R15") (pin "2") (pinfunction "2_2") (pintype "passive"))
    )
    (net (code "55") (name "Net-(E1A-EMIT)") (class "Default")
      (node (ref "E1") (pin "16") (pinfunction "EMIT_16") (pintype "passive"))
      (node (ref "R21") (pin "2") (pinfunction "2_2") (pintype "passive"))
      (node (ref "R23") (pin "2") (pinfunction "2_2") (pintype "passive"))
    )
    (net (code "56") (name "Net-(E1C-A)") (class "Default")
      (node (ref "E1") (pin "5") (pinfunction "A_5") (pintype "passive"))
      (node (ref "R10") (pin "1") (pinfunction "1_1") (pintype "passive"))
    )
    (net (code "57") (name "Net-(E3A-C1+)") (class "Default")
      (node (ref "C14") (pin "1") (pinfunction "1_1") (pintype "passive"))
      (node (ref "E3") (pin "1") (pinfunction "C1+_1") (pintype "bidirectional"))
    )
    (net (code "58") (name "Net-(E3A-C1-)") (class "Default")
      (node (ref "C14") (pin "2") (pinfunction "2_2") (pintype "passive"))
      (node (ref "E3") (pin "3") (pinfunction "C1-_3") (pintype "bidirectional"))
    )
    (net (code "59") (name "Net-(E3A-C2+)") (class "Default")
      (node (ref "C15") (pin "1") (pinfunction "1_1") (pintype "passive"))
      (node (ref "E3") (pin "4") (pinfunction "C2+_4") (pintype "bidirectional"))
    )
    (net (code "60") (name "Net-(E3A-C2-)") (class "Default")
      (node (ref "C15") (pin "2") (pinfunction "2_2") (pintype "passive"))
      (node (ref "E3") (pin "5") (pinfunction "C2-_5") (pintype "bidirectional"))
    )
    (net (code "61") (name "Net-(E3A-V+)") (class "Default")
      (node (ref "C16") (pin "1") (pinfunction "1_1") (pintype "passive"))
      (node (ref "E3") (pin "2") (pinfunction "V+_2") (pintype "bidirectional"))
    )
    (net (code "62") (name "Net-(E3A-V-)") (class "Default")
      (node (ref "C17") (pin "2") (pinfunction "2_2") (pintype "passive"))
      (node (ref "E3") (pin "6") (pinfunction "V-_6") (pintype "bidirectional"))
    )
    (net (code "63") (name "Net-(E4A-QA)") (class "Default")
      (node (ref "E4") (pin "3") (pinfunction "QA_3") (pintype "output"))
      (node (ref "E7") (pin "2") (pinfunction "I1_2") (pintype "input"))
    )
    (net (code "64") (name "Net-(E4A-QB)") (class "Default")
      (node (ref "E4") (pin "4") (pinfunction "QB_4") (pintype "output"))
      (node (ref "E7") (pin "1") (pinfunction "I0_1") (pintype "input"))
    )
    (net (code "65") (name "Net-(E6A-I2)") (class "Default")
      (node (ref "E6") (pin "3") (pinfunction "I2_3") (pintype "input"))
      (node (ref "TX3") (pin "2") (pinfunction "2_2") (pintype "passive"))
    )
    (net (code "66") (name "Net-(E6A-I3)") (class "Default")
      (node (ref "E6") (pin "4") (pinfunction "I3_4") (pintype "input"))
      (node (ref "TX4") (pin "2") (pinfunction "2_2") (pintype "passive"))
    )
    (net (code "67") (name "Net-(E6A-I4)") (class "Default")
      (node (ref "E6") (pin "5") (pinfunction "I4_5") (pintype "input"))
      (node (ref "TX5") (pin "2") (pinfunction "2_2") (pintype "passive"))
    )
    (net (code "68") (name "Net-(E6A-I5)") (class "Default")
      (node (ref "E6") (pin "6") (pinfunction "I5_6") (pintype "input"))
      (node (ref "TX6") (pin "2") (pinfunction "2_2") (pintype "passive"))
    )
    (net (code "69") (name "Net-(E6A-I6)") (class "Default")
      (node (ref "E6") (pin "11") (pinfunction "I6_11") (pintype "input"))
      (node (ref "TX7") (pin "2") (pinfunction "2_2") (pintype "passive"))
    )
    (net (code "70") (name "Net-(E6A-I7)") (class "Default")
      (node (ref "E6") (pin "12") (pinfunction "I7_12") (pintype "input"))
      (node (ref "TX8") (pin "2") (pinfunction "2_2") (pintype "passive"))
    )
    (net (code "71") (name "Net-(E6A-O)") (class "Default")
      (node (ref "E6") (pin "8") (pinfunction "O_8") (pintype "output"))
      (node (ref "E9") (pin "13") (pinfunction "I_13") (pintype "input"))
    )
    (net (code "72") (name "Net-(E8A-I2)") (class "Default")
      (node (ref "E8") (pin "3") (pinfunction "I2_3") (pintype "input"))
      (node (ref "RX3") (pin "2") (pinfunction "2_2") (pintype "passive"))
    )
    (net (code "73") (name "Net-(E8A-I3)") (class "Default")
      (node (ref "E8") (pin "4") (pinfunction "I3_4") (pintype "input"))
      (node (ref "RX4") (pin "2") (pinfunction "2_2") (pintype "passive"))
    )
    (net (code "74") (name "Net-(E8A-I4)") (class "Default")
      (node (ref "E8") (pin "5") (pinfunction "I4_5") (pintype "input"))
      (node (ref "RX5") (pin "2") (pinfunction "2_2") (pintype "passive"))
    )
    (net (code "75") (name "Net-(E8A-I5)") (class "Default")
      (node (ref "E8") (pin "6") (pinfunction "I5_6") (pintype "input"))
      (node (ref "RX6") (pin "2") (pinfunction "2_2") (pintype "passive"))
    )
    (net (code "76") (name "Net-(E8A-I6)") (class "Default")
      (node (ref "E8") (pin "11") (pinfunction "I6_11") (pintype "input"))
      (node (ref "RX7") (pin "2") (pinfunction "2_2") (pintype "passive"))
    )
    (net (code "77") (name "Net-(E8A-I7)") (class "Default")
      (node (ref "E8") (pin "12") (pinfunction "I7_12") (pintype "input"))
      (node (ref "RX8") (pin "2") (pinfunction "2_2") (pintype "passive"))
    )
    (net (code "78") (name "Net-(E8A-O)") (class "Default")
      (node (ref "E8") (pin "8") (pinfunction "O_8") (pintype "output"))
      (node (ref "E9") (pin "1") (pinfunction "I_1") (pintype "input"))
    )
    (net (code "79") (name "READER_RUN+") (class "Default")
      (node (ref "J1") (pin "PP") (pinfunction "35_PP") (pintype "bidirectional"))
      (node (ref "R21") (pin "1") (pinfunction "1_1") (pintype "passive"))
      (node (ref "R23") (pin "1") (pinfunction "1_1") (pintype "passive"))
      (node (ref "R6") (pin "2") (pinfunction "2_2") (pintype "passive"))
    )
    (net (code "80") (name "RTS") (class "Default")
      (node (ref "E3") (pin "14") (pinfunction "T1OUT_14") (pintype "output"))
      (node (ref "J1") (pin "V") (pinfunction "18_V") (pintype "bidirectional"))
    )
    (net (code "81") (name "RUN") (class "Default")
      (node (ref "IOB") (pin "S2") (pinfunction "1_S2") (pintype "bidirectional"))
    )
    (net (code "82") (name "RX20MA_DATA") (class "Default")
      (node (ref "E1") (pin "10") (pinfunction "COL_10") (pintype "passive"))
      (node (ref "J1") (pin "H") (pinfunction "7_H") (pintype "bidirectional"))
      (node (ref "R1") (pin "1") (pinfunction "1_1") (pintype "passive"))
    )
    (net (code "83") (name "RXD232") (class "Default")
      (node (ref "E3") (pin "8") (pinfunction "R2IN_8") (pintype "input"))
      (node (ref "J1") (pin "J") (pinfunction "8_J") (pintype "bidirectional"))
    )
    (net (code "84") (name "RXDTTL") (class "Default")
      (node (ref "E3") (pin "9") (pinfunction "R2OUT_9") (pintype "output"))
      (node (ref "J1") (pin "M") (pinfunction "11_M") (pintype "bidirectional"))
    )
    (net (code "85") (name "RX_20MA+") (class "Default")
      (node (ref "D1") (pin "C") (pinfunction "C_C") (pintype "passive"))
      (node (ref "J1") (pin "K") (pinfunction "9_K") (pintype "bidirectional"))
      (node (ref "R3") (pin "1") (pinfunction "1_1") (pintype "passive"))
    )
    (net (code "86") (name "RX_20MA-") (class "Default")
      (node (ref "D1") (pin "A") (pinfunction "A_A") (pintype "passive"))
      (node (ref "E1") (pin "8") (pinfunction "A_8") (pintype "passive"))
      (node (ref "J1") (pin "S") (pinfunction "15_S") (pintype "bidirectional"))
    )
    (net (code "87") (name "RX_DATA") (class "Default")
      (node (ref "E2") (pin "27") (pinfunction "IO20_27") (pintype "bidirectional"))
      (node (ref "J1") (pin "E") (pinfunction "5_E") (pintype "bidirectional"))
    )
    (net (code "88") (name "RX_RATE") (class "Default")
      (node (ref "E11") (pin "2") (pinfunction "IN/OE2/GCLK2_2") (pintype "input"))
      (node (ref "E2") (pin "2") (pinfunction "IN/OE2/GCLK2_2") (pintype "input"))
      (node (ref "E2") (pin "43") (pinfunction "IN/GCLK1_43") (pintype "input"))
      (node (ref "SV1") (pin "8") (pinfunction "8_8") (pintype "passive"))
      (node (ref "SV2") (pin "8") (pinfunction "8_8") (pintype "passive"))
      (node (ref "SV3") (pin "8") (pinfunction "8_8") (pintype "passive"))
      (node (ref "TX_RATE1") (pin "3") (pinfunction "3_3") (pintype "passive"))
    )
    (net (code "89") (name "RX_SEL") (class "Default")
      (node (ref "E11") (pin "26") (pinfunction "IO19_26") (pintype "bidirectional"))
      (node (ref "E2") (pin "26") (pinfunction "IO19_26") (pintype "bidirectional"))
      (node (ref "E9") (pin "2") (pinfunction "O_2") (pintype "output"))
      (node (ref "SV1") (pin "12") (pinfunction "12_12") (pintype "passive"))
      (node (ref "SV2") (pin "12") (pinfunction "12_12") (pintype "passive"))
      (node (ref "SV3") (pin "12") (pinfunction "12_12") (pintype "passive"))
    )
    (net (code "90") (name "R_RUN") (class "Default")
      (node (ref "E1") (pin "1") (pinfunction "A_1") (pintype "passive"))
      (node (ref "E3") (pin "11") (pinfunction "T1IN_11") (pintype "input"))
    )
    (net (code "91") (name "STOP1") (class "Default")
      (node (ref "E11") (pin "37") (pinfunction "IO30_37") (pintype "bidirectional"))
      (node (ref "STPBIT1") (pin "3") (pinfunction "3_3") (pintype "passive"))
    )
    (net (code "92") (name "STOP2") (class "Default")
      (node (ref "E11") (pin "39") (pinfunction "IO31_39") (pintype "bidirectional"))
      (node (ref "STPBIT1") (pin "1") (pinfunction "1_1") (pintype "passive"))
    )
    (net (code "93") (name "STP_MARK") (class "Default")
      (node (ref "E11") (pin "44") (pinfunction "IN/OE1_44") (pintype "input"))
      (node (ref "STPBIT1") (pin "2") (pinfunction "2_2") (pintype "passive"))
    )
    (net (code "94") (name "TCKE2") (class "Default")
      (node (ref "E2") (pin "32") (pinfunction "IO21/TCK_32") (pintype "bidirectional"))
      (node (ref "PGM") (pin "1") (pinfunction "1_1") (pintype "passive"))
    )
    (net (code "95") (name "TCKE11") (class "Default")
      (node (ref "E11") (pin "32") (pinfunction "IO21/TCK_32") (pintype "bidirectional"))
      (node (ref "PGM1") (pin "1") (pinfunction "1_1") (pintype "passive"))
    )
    (net (code "96") (name "TDIE2") (class "Default")
      (node (ref "E2") (pin "7") (pinfunction "IO1/TDI_7") (pintype "bidirectional"))
      (node (ref "PGM") (pin "9") (pinfunction "9_9") (pintype "passive"))
    )
    (net (code "97") (name "TDIE11") (class "Default")
      (node (ref "E11") (pin "7") (pinfunction "IO1/TDI_7") (pintype "bidirectional"))
      (node (ref "PGM1") (pin "9") (pinfunction "9_9") (pintype "passive"))
    )
    (net (code "98") (name "TDOE2") (class "Default")
      (node (ref "E2") (pin "38") (pinfunction "IO26/TDO_38") (pintype "bidirectional"))
      (node (ref "PGM") (pin "3") (pinfunction "3_3") (pintype "passive"))
    )
    (net (code "99") (name "TDOE11") (class "Default")
      (node (ref "E11") (pin "38") (pinfunction "IO26/TDO_38") (pintype "bidirectional"))
      (node (ref "PGM1") (pin "3") (pinfunction "3_3") (pintype "passive"))
    )
    (net (code "100") (name "TMSE2") (class "Default")
      (node (ref "E2") (pin "13") (pinfunction "IO6/TMS_13") (pintype "bidirectional"))
      (node (ref "PGM") (pin "5") (pinfunction "5_5") (pintype "passive"))
    )
    (net (code "101") (name "TMSE11") (class "Default")
      (node (ref "E11") (pin "13") (pinfunction "IO6/TMS_13") (pintype "bidirectional"))
      (node (ref "PGM1") (pin "5") (pinfunction "5_5") (pintype "passive"))
    )
    (net (code "102") (name "TXD232") (class "Default")
      (node (ref "E3") (pin "7") (pinfunction "T2OUT_7") (pintype "output"))
      (node (ref "J1") (pin "F") (pinfunction "6_F") (pintype "bidirectional"))
    )
    (net (code "103") (name "TXDTTL") (class "Default")
      (node (ref "E11") (pin "36") (pinfunction "IO28_36") (pintype "bidirectional"))
      (node (ref "E2") (pin "36") (pinfunction "IO28_36") (pintype "bidirectional"))
      (node (ref "E3") (pin "10") (pinfunction "T2IN_10") (pintype "input"))
      (node (ref "R10") (pin "2") (pinfunction "2_2") (pintype "passive"))
      (node (ref "SV1") (pin "10") (pinfunction "10_10") (pintype "passive"))
      (node (ref "SV2") (pin "10") (pinfunction "10_10") (pintype "passive"))
      (node (ref "SV3") (pin "10") (pinfunction "10_10") (pintype "passive"))
    )
    (net (code "104") (name "TX_20MA+") (class "Default")
      (node (ref "J1") (pin "AA") (pinfunction "23_AA") (pintype "bidirectional"))
      (node (ref "R4") (pin "2") (pinfunction "2_2") (pintype "passive"))
    )
    (net (code "105") (name "TX_20MA-") (class "Default")
      (node (ref "E1") (pin "11") (pinfunction "COL_11") (pintype "passive"))
      (node (ref "J1") (pin "KK") (pinfunction "31_KK") (pintype "bidirectional"))
    )
    (net (code "106") (name "TX_RATEI") (class "Default")
      (node (ref "E11") (pin "43") (pinfunction "IN/GCLK1_43") (pintype "input"))
      (node (ref "TX_RATE1") (pin "2") (pinfunction "2_2") (pintype "passive"))
    )
    (net (code "107") (name "TX_RATEO") (class "Default")
      (node (ref "E11") (pin "41") (pinfunction "IO29/GCLK3_41") (pintype "bidirectional"))
      (node (ref "TX_RATE1") (pin "1") (pinfunction "1_1") (pintype "passive"))
    )
    (net (code "108") (name "TX_SEL") (class "Default")
      (node (ref "E11") (pin "31") (pinfunction "IO24_31") (pintype "bidirectional"))
      (node (ref "E2") (pin "31") (pinfunction "IO24_31") (pintype "bidirectional"))
      (node (ref "E9") (pin "12") (pinfunction "O_12") (pintype "output"))
      (node (ref "SV1") (pin "11") (pinfunction "11_11") (pintype "passive"))
      (node (ref "SV2") (pin "11") (pinfunction "11_11") (pintype "passive"))
      (node (ref "SV3") (pin "11") (pinfunction "11_11") (pintype "passive"))
    )
    (net (code "109") (name "VCC") (class "Default")
      (node (ref "BAC") (pin "A2") (pinfunction "1_A2") (pintype "bidirectional"))
      (node (ref "BMB") (pin "A2") (pinfunction "1_A2") (pintype "bidirectional"))
      (node (ref "C1") (pin "1") (pinfunction "1_1") (pintype "passive"))
      (node (ref "C10") (pin "1") (pinfunction "1_1") (pintype "passive"))
      (node (ref "C11") (pin "1") (pinfunction "1_1") (pintype "passive"))
      (node (ref "C12") (pin "1") (pinfunction "1_1") (pintype "passive"))
      (node (ref "C13") (pin "1") (pinfunction "1_1") (pintype "passive"))
      (node (ref "C16") (pin "2") (pinfunction "2_2") (pintype "passive"))
      (node (ref "C18") (pin "1") (pinfunction "1_1") (pintype "passive"))
      (node (ref "C19") (pin "1") (pinfunction "1_1") (pintype "passive"))
      (node (ref "C2") (pin "1") (pinfunction "1_1") (pintype "passive"))
      (node (ref "C20") (pin "+") (pinfunction "+_+") (pintype "passive"))
      (node (ref "C21") (pin "+") (pinfunction "+_+") (pintype "passive"))
      (node (ref "C22") (pin "+") (pinfunction "+_+") (pintype "passive"))
      (node (ref "C3") (pin "1") (pinfunction "1_1") (pintype "passive"))
      (node (ref "C4") (pin "1") (pinfunction "1_1") (pintype "passive"))
      (node (ref "C5") (pin "1") (pinfunction "1_1") (pintype "passive"))
      (node (ref "C6") (pin "1") (pinfunction "1_1") (pintype "passive"))
      (node (ref "C7") (pin "1") (pinfunction "1_1") (pintype "passive"))
      (node (ref "C8") (pin "1") (pinfunction "1_1") (pintype "passive"))
      (node (ref "C9") (pin "1") (pinfunction "1_1") (pintype "passive"))
      (node (ref "E1") (pin "15") (pinfunction "COL_15") (pintype "passive"))
      (node (ref "E2") (pin "44") (pinfunction "IN/OE1_44") (pintype "input"))
      (node (ref "E6") (pin "1") (pinfunction "I0_1") (pintype "input"))
      (node (ref "E6") (pin "2") (pinfunction "I1_2") (pintype "input"))
      (node (ref "E8") (pin "1") (pinfunction "I0_1") (pintype "input"))
      (node (ref "E8") (pin "2") (pinfunction "I1_2") (pintype "input"))
      (node (ref "IOB") (pin "A2") (pinfunction "1_A2") (pintype "bidirectional"))
      (node (ref "OSC") (pin "8") (pinfunction "VCC_8") (pintype "power_in"))
      (node (ref "OSC1") (pin "14") (pinfunction "VCC_14") (pintype "power_in"))
      (node (ref "PGM") (pin "4") (pinfunction "4_4") (pintype "passive"))
      (node (ref "PGM1") (pin "4") (pinfunction "4_4") (pintype "passive"))
      (node (ref "R1") (pin "2") (pinfunction "2_2") (pintype "passive"))
      (node (ref "R3") (pin "2") (pinfunction "2_2") (pintype "passive"))
      (node (ref "R4") (pin "1") (pinfunction "1_1") (pintype "passive"))
    )
    (net (code "110") (name "X8_RATE") (class "Default")
      (node (ref "BAUD") (pin "10") (pinfunction "10_10") (pintype "passive"))
      (node (ref "BAUD") (pin "12") (pinfunction "12_12") (pintype "passive"))
      (node (ref "BAUD") (pin "14") (pinfunction "14_14") (pintype "passive"))
      (node (ref "BAUD") (pin "16") (pinfunction "16_16") (pintype "passive"))
      (node (ref "BAUD") (pin "18") (pinfunction "18_18") (pintype "passive"))
      (node (ref "BAUD") (pin "2") (pinfunction "2_2") (pintype "passive"))
      (node (ref "BAUD") (pin "20") (pinfunction "20_20") (pintype "passive"))
      (node (ref "BAUD") (pin "22") (pinfunction "22_22") (pintype "passive"))
      (node (ref "BAUD") (pin "24") (pinfunction "24_24") (pintype "passive"))
      (node (ref "BAUD") (pin "26") (pinfunction "26_26") (pintype "passive"))
      (node (ref "BAUD") (pin "4") (pinfunction "4_4") (pintype "passive"))
      (node (ref "BAUD") (pin "6") (pinfunction "6_6") (pintype "passive"))
      (node (ref "BAUD") (pin "8") (pinfunction "8_8") (pintype "passive"))
    )
    (net (code "111") (name "unconnected-(E1B-A-Pad4)") (class "Default")
      (node (ref "E1") (pin "4") (pinfunction "A_4") (pintype "passive"))
    )
    (net (code "112") (name "unconnected-(E1B-C-Pad3)") (class "Default")
      (node (ref "E1") (pin "3") (pinfunction "C_3") (pintype "passive"))
    )
    (net (code "113") (name "unconnected-(E1B-COL-Pad14)") (class "Default")
      (node (ref "E1") (pin "14") (pinfunction "COL_14") (pintype "passive"))
    )
    (net (code "114") (name "unconnected-(E2A-IO2-Pad4)") (class "Default")
      (node (ref "E2") (pin "4") (pinfunction "IO2_4") (pintype "bidirectional"))
    )
    (net (code "115") (name "unconnected-(E2A-IO29{slash}GCLK3-Pad41)") (class "Default")
      (node (ref "E2") (pin "41") (pinfunction "IO29/GCLK3_41") (pintype "bidirectional"))
    )
    (net (code "116") (name "unconnected-(E2A-IO30-Pad37)") (class "Default")
      (node (ref "E2") (pin "37") (pinfunction "IO30_37") (pintype "bidirectional"))
    )
    (net (code "117") (name "unconnected-(E2A-IO31-Pad39)") (class "Default")
      (node (ref "E2") (pin "39") (pinfunction "IO31_39") (pintype "bidirectional"))
    )
    (net (code "118") (name "unconnected-(E4A-QC-Pad5)") (class "Default")
      (node (ref "E4") (pin "5") (pinfunction "QC_5") (pintype "output"))
    )
    (net (code "119") (name "unconnected-(E10A-QD-Pad6)") (class "Default")
      (node (ref "E10") (pin "6") (pinfunction "QD_6") (pintype "output"))
    )
    (net (code "120") (name "unconnected-(E11A-IO20-Pad27)") (class "Default")
      (node (ref "E11") (pin "27") (pinfunction "IO20_27") (pintype "bidirectional"))
    )
    (net (code "121") (name "unconnected-(E11A-IO27-Pad34)") (class "Default")
      (node (ref "E11") (pin "34") (pinfunction "IO27_34") (pintype "bidirectional"))
    )
    (net (code "122") (name "unconnected-(E11A-IO32-Pad40)") (class "Default")
      (node (ref "E11") (pin "40") (pinfunction "IO32_40") (pintype "bidirectional"))
    )
    (net (code "123") (name "unconnected-(J1-4-PadD)") (class "Default")
      (node (ref "J1") (pin "D") (pinfunction "4_D") (pintype "bidirectional"))
    )
    (net (code "124") (name "unconnected-(J1-10-PadL)") (class "Default")
      (node (ref "J1") (pin "L") (pinfunction "10_L") (pintype "bidirectional"))
    )
    (net (code "125") (name "unconnected-(J1-12-PadN)") (class "Default")
      (node (ref "J1") (pin "N") (pinfunction "12_N") (pintype "bidirectional"))
    )
    (net (code "126") (name "unconnected-(J1-13-PadP)") (class "Default")
      (node (ref "J1") (pin "P") (pinfunction "13_P") (pintype "bidirectional"))
    )
    (net (code "127") (name "unconnected-(J1-14-PadR)") (class "Default")
      (node (ref "J1") (pin "R") (pinfunction "14_R") (pintype "bidirectional"))
    )
    (net (code "128") (name "unconnected-(J1-16-PadT)") (class "Default")
      (node (ref "J1") (pin "T") (pinfunction "16_T") (pintype "bidirectional"))
    )
    (net (code "129") (name "unconnected-(J1-17-PadU)") (class "Default")
      (node (ref "J1") (pin "U") (pinfunction "17_U") (pintype "bidirectional"))
    )
    (net (code "130") (name "unconnected-(J1-19-PadW)") (class "Default")
      (node (ref "J1") (pin "W") (pinfunction "19_W") (pintype "bidirectional"))
    )
    (net (code "131") (name "unconnected-(J1-20-PadX)") (class "Default")
      (node (ref "J1") (pin "X") (pinfunction "20_X") (pintype "bidirectional"))
    )
    (net (code "132") (name "unconnected-(J1-21-PadY)") (class "Default")
      (node (ref "J1") (pin "Y") (pinfunction "21_Y") (pintype "bidirectional"))
    )
    (net (code "133") (name "unconnected-(J1-22-PadZ)") (class "Default")
      (node (ref "J1") (pin "Z") (pinfunction "22_Z") (pintype "bidirectional"))
    )
    (net (code "134") (name "unconnected-(J1-24-PadBB)") (class "Default")
      (node (ref "J1") (pin "BB") (pinfunction "24_BB") (pintype "bidirectional"))
    )
    (net (code "135") (name "unconnected-(J1-25-PadCC)") (class "Default")
      (node (ref "J1") (pin "CC") (pinfunction "25_CC") (pintype "bidirectional"))
    )
    (net (code "136") (name "unconnected-(J1-28-PadFF)") (class "Default")
      (node (ref "J1") (pin "FF") (pinfunction "28_FF") (pintype "bidirectional"))
    )
    (net (code "137") (name "unconnected-(J1-29-PadHH)") (class "Default")
      (node (ref "J1") (pin "HH") (pinfunction "29_HH") (pintype "bidirectional"))
    )
    (net (code "138") (name "unconnected-(J1-30-PadJJ)") (class "Default")
      (node (ref "J1") (pin "JJ") (pinfunction "30_JJ") (pintype "bidirectional"))
    )
    (net (code "139") (name "unconnected-(J1-32-PadLL)") (class "Default")
      (node (ref "J1") (pin "LL") (pinfunction "32_LL") (pintype "bidirectional"))
    )
    (net (code "140") (name "unconnected-(J1-33-PadMM)") (class "Default")
      (node (ref "J1") (pin "MM") (pinfunction "33_MM") (pintype "bidirectional"))
    )
    (net (code "141") (name "unconnected-(J1-34-PadNN)") (class "Default")
      (node (ref "J1") (pin "NN") (pinfunction "34_NN") (pintype "bidirectional"))
    )
    (net (code "142") (name "unconnected-(J1-36-PadRR)") (class "Default")
      (node (ref "J1") (pin "RR") (pinfunction "36_RR") (pintype "bidirectional"))
    )
    (net (code "143") (name "unconnected-(J1-37-PadSS)") (class "Default")
      (node (ref "J1") (pin "SS") (pinfunction "37_SS") (pintype "bidirectional"))
    )
    (net (code "144") (name "unconnected-(J1-38-PadTT)") (class "Default")
      (node (ref "J1") (pin "TT") (pinfunction "38_TT") (pintype "bidirectional"))
    )
    (net (code "145") (name "unconnected-(PGM-Pad6)") (class "Default")
      (node (ref "PGM") (pin "6") (pinfunction "6_6") (pintype "passive"))
    )
    (net (code "146") (name "unconnected-(PGM-Pad7)") (class "Default")
      (node (ref "PGM") (pin "7") (pinfunction "7_7") (pintype "passive"))
    )
    (net (code "147") (name "unconnected-(PGM-Pad8)") (class "Default")
      (node (ref "PGM") (pin "8") (pinfunction "8_8") (pintype "passive"))
    )
    (net (code "148") (name "unconnected-(PGM1-Pad6)") (class "Default")
      (node (ref "PGM1") (pin "6") (pinfunction "6_6") (pintype "passive"))
    )
    (net (code "149") (name "unconnected-(PGM1-Pad7)") (class "Default")
      (node (ref "PGM1") (pin "7") (pinfunction "7_7") (pintype "passive"))
    )
    (net (code "150") (name "unconnected-(PGM1-Pad8)") (class "Default")
      (node (ref "PGM1") (pin "8") (pinfunction "8_8") (pintype "passive"))
    )
    (net (code "151") (name "~{ACCLR}") (class "Default")
      (node (ref "E2") (pin "34") (pinfunction "IO27_34") (pintype "bidirectional"))
      (node (ref "IOB") (pin "P2") (pinfunction "1_P2") (pintype "bidirectional"))
    )
    (net (code "152") (name "~{BMB3}") (class "Default")
      (node (ref "BMB") (pin "H1") (pinfunction "1_H1") (pintype "bidirectional"))
      (node (ref "RX3") (pin "1") (pinfunction "1_1") (pintype "passive"))
      (node (ref "TX3") (pin "1") (pinfunction "1_1") (pintype "passive"))
    )
    (net (code "153") (name "~{BMB4}") (class "Default")
      (node (ref "BMB") (pin "L1") (pinfunction "1_L1") (pintype "bidirectional"))
      (node (ref "RX4") (pin "1") (pinfunction "1_1") (pintype "passive"))
      (node (ref "TX4") (pin "1") (pinfunction "1_1") (pintype "passive"))
    )
    (net (code "154") (name "~{BMB5}") (class "Default")
      (node (ref "BMB") (pin "P1") (pinfunction "1_P1") (pintype "bidirectional"))
      (node (ref "RX5") (pin "1") (pinfunction "1_1") (pintype "passive"))
      (node (ref "TX5") (pin "1") (pinfunction "1_1") (pintype "passive"))
    )
    (net (code "155") (name "~{BMB6}") (class "Default")
      (node (ref "BMB") (pin "D2") (pinfunction "1_D2") (pintype "bidirectional"))
      (node (ref "RX6") (pin "1") (pinfunction "1_1") (pintype "passive"))
      (node (ref "TX6") (pin "1") (pinfunction "1_1") (pintype "passive"))
    )
    (net (code "156") (name "~{BMB7}") (class "Default")
      (node (ref "BMB") (pin "H2") (pinfunction "1_H2") (pintype "bidirectional"))
      (node (ref "RX7") (pin "1") (pinfunction "1_1") (pintype "passive"))
      (node (ref "TX7") (pin "1") (pinfunction "1_1") (pintype "passive"))
    )
    (net (code "157") (name "~{BMB8}") (class "Default")
      (node (ref "BMB") (pin "M2") (pinfunction "1_M2") (pintype "bidirectional"))
      (node (ref "RX8") (pin "1") (pinfunction "1_1") (pintype "passive"))
      (node (ref "TX8") (pin "1") (pinfunction "1_1") (pintype "passive"))
    )
    (net (code "158") (name "~{INIT}") (class "Default")
      (node (ref "E11") (pin "33") (pinfunction "IO25_33") (pintype "bidirectional"))
      (node (ref "E2") (pin "1") (pinfunction "IN/GCLR_1") (pintype "input"))
      (node (ref "E2") (pin "33") (pinfunction "IO25_33") (pintype "bidirectional"))
      (node (ref "SV1") (pin "3") (pinfunction "3_3") (pintype "passive"))
      (node (ref "SV2") (pin "3") (pinfunction "3_3") (pintype "passive"))
      (node (ref "SV3") (pin "3") (pinfunction "3_3") (pintype "passive"))
    )
    (net (code "159") (name "~{IOB0}") (class "Default")
      (node (ref "E2") (pin "24") (pinfunction "IO18_24") (pintype "bidirectional"))
      (node (ref "IOB") (pin "B1") (pinfunction "1_B1") (pintype "bidirectional"))
    )
    (net (code "160") (name "~{IOB1}") (class "Default")
      (node (ref "E2") (pin "20") (pinfunction "IO16_20") (pintype "bidirectional"))
      (node (ref "IOB") (pin "D1") (pinfunction "1_D1") (pintype "bidirectional"))
    )
    (net (code "161") (name "~{IOB2}") (class "Default")
      (node (ref "E2") (pin "19") (pinfunction "IO14_19") (pintype "bidirectional"))
      (node (ref "IOB") (pin "E1") (pinfunction "1_E1") (pintype "bidirectional"))
    )
    (net (code "162") (name "~{IOB3}") (class "Default")
      (node (ref "E2") (pin "17") (pinfunction "IO12_17") (pintype "bidirectional"))
      (node (ref "IOB") (pin "H1") (pinfunction "1_H1") (pintype "bidirectional"))
    )
    (net (code "163") (name "~{IOB4}") (class "Default")
      (node (ref "E2") (pin "16") (pinfunction "IO11_16") (pintype "bidirectional"))
      (node (ref "IOB") (pin "J1") (pinfunction "1_J1") (pintype "bidirectional"))
    )
    (net (code "164") (name "~{IOB5}") (class "Default")
      (node (ref "E2") (pin "11") (pinfunction "IO4/PD1_11") (pintype "bidirectional"))
      (node (ref "IOB") (pin "L1") (pinfunction "1_L1") (pintype "bidirectional"))
    )
    (net (code "165") (name "~{IOB6}") (class "Default")
      (node (ref "E2") (pin "12") (pinfunction "IO9_12") (pintype "bidirectional"))
      (node (ref "IOB") (pin "M1") (pinfunction "1_M1") (pintype "bidirectional"))
    )
    (net (code "166") (name "~{IOB7}") (class "Default")
      (node (ref "E2") (pin "8") (pinfunction "IO7_8") (pintype "bidirectional"))
      (node (ref "IOB") (pin "P1") (pinfunction "1_P1") (pintype "bidirectional"))
    )
    (net (code "167") (name "~{IOB8}") (class "Default")
      (node (ref "E2") (pin "5") (pinfunction "IO3_5") (pintype "bidirectional"))
      (node (ref "IOB") (pin "S1") (pinfunction "1_S1") (pintype "bidirectional"))
    )
    (net (code "168") (name "~{IOB9}") (class "Default")
      (node (ref "E2") (pin "25") (pinfunction "IO15/PD2_25") (pintype "bidirectional"))
      (node (ref "IOB") (pin "D2") (pinfunction "1_D2") (pintype "bidirectional"))
    )
    (net (code "169") (name "~{IOB10}") (class "Default")
      (node (ref "E2") (pin "21") (pinfunction "IO17_21") (pintype "bidirectional"))
      (node (ref "IOB") (pin "E2") (pinfunction "1_E2") (pintype "bidirectional"))
    )
    (net (code "170") (name "~{IOB11}") (class "Default")
      (node (ref "E2") (pin "18") (pinfunction "IO13_18") (pintype "bidirectional"))
      (node (ref "IOB") (pin "H2") (pinfunction "1_H2") (pintype "bidirectional"))
    )
    (net (code "171") (name "~{IRQ}") (class "Default")
      (node (ref "E11") (pin "29") (pinfunction "IO23_29") (pintype "bidirectional"))
      (node (ref "E2") (pin "29") (pinfunction "IO23_29") (pintype "bidirectional"))
      (node (ref "IOB") (pin "M2") (pinfunction "1_M2") (pintype "bidirectional"))
      (node (ref "SV1") (pin "4") (pinfunction "4_4") (pintype "passive"))
      (node (ref "SV2") (pin "4") (pinfunction "4_4") (pintype "passive"))
      (node (ref "SV3") (pin "4") (pinfunction "4_4") (pintype "passive"))
    )
    (net (code "172") (name "~{SKIP}") (class "Default")
      (node (ref "E11") (pin "28") (pinfunction "IO22_28") (pintype "bidirectional"))
      (node (ref "E2") (pin "28") (pinfunction "IO22_28") (pintype "bidirectional"))
      (node (ref "IOB") (pin "K2") (pinfunction "1_K2") (pintype "bidirectional"))
      (node (ref "SV1") (pin "6") (pinfunction "6_6") (pintype "passive"))
      (node (ref "SV2") (pin "6") (pinfunction "6_6") (pintype "passive"))
      (node (ref "SV3") (pin "6") (pinfunction "6_6") (pintype "passive"))
    )
  )
)
